# Edin_Usher_V2_0_ERM.net
KiCad netlist of a schematic drawn in EAGLE
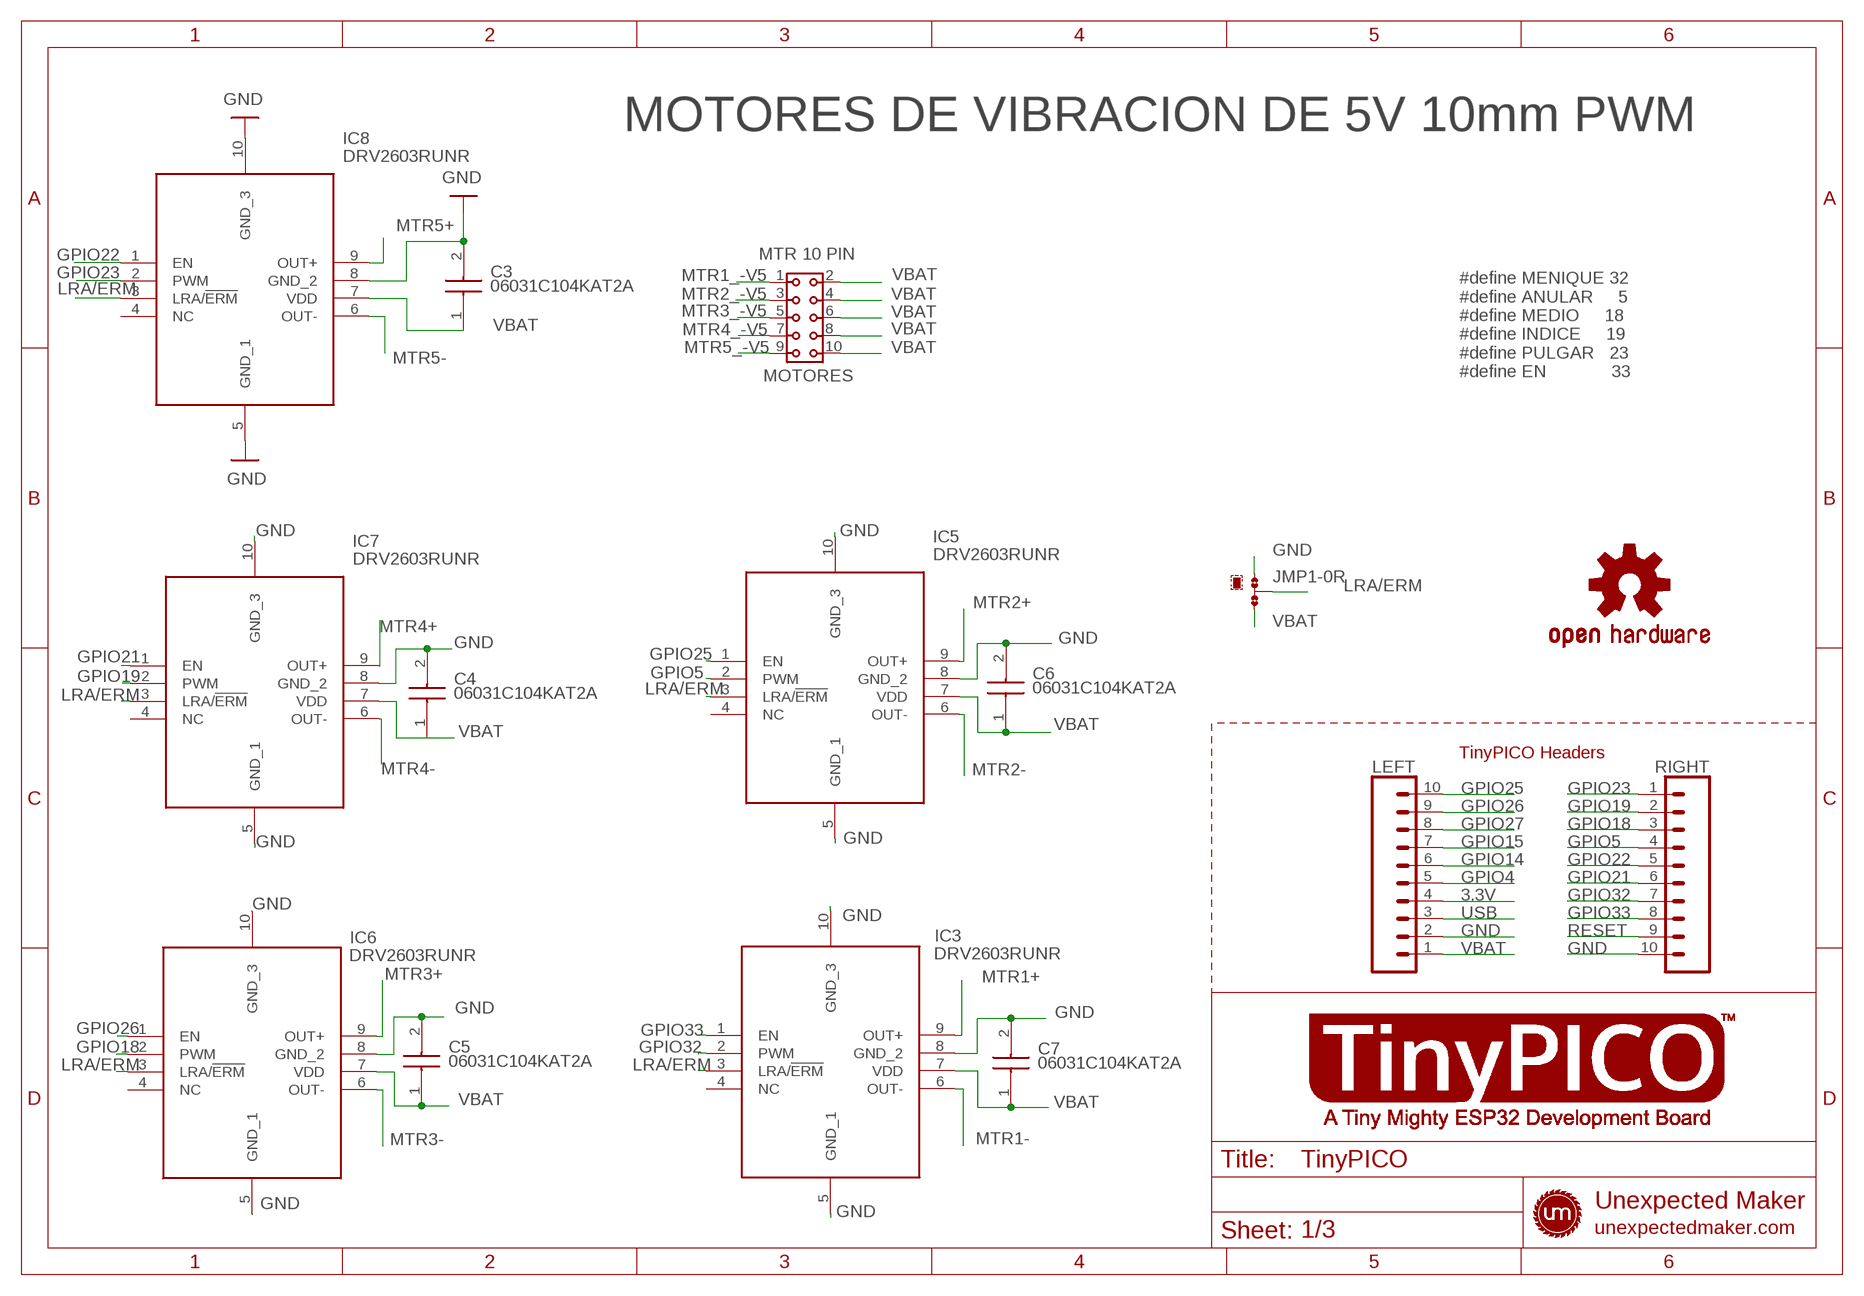
[diagram p0: schematic, sheet 1]
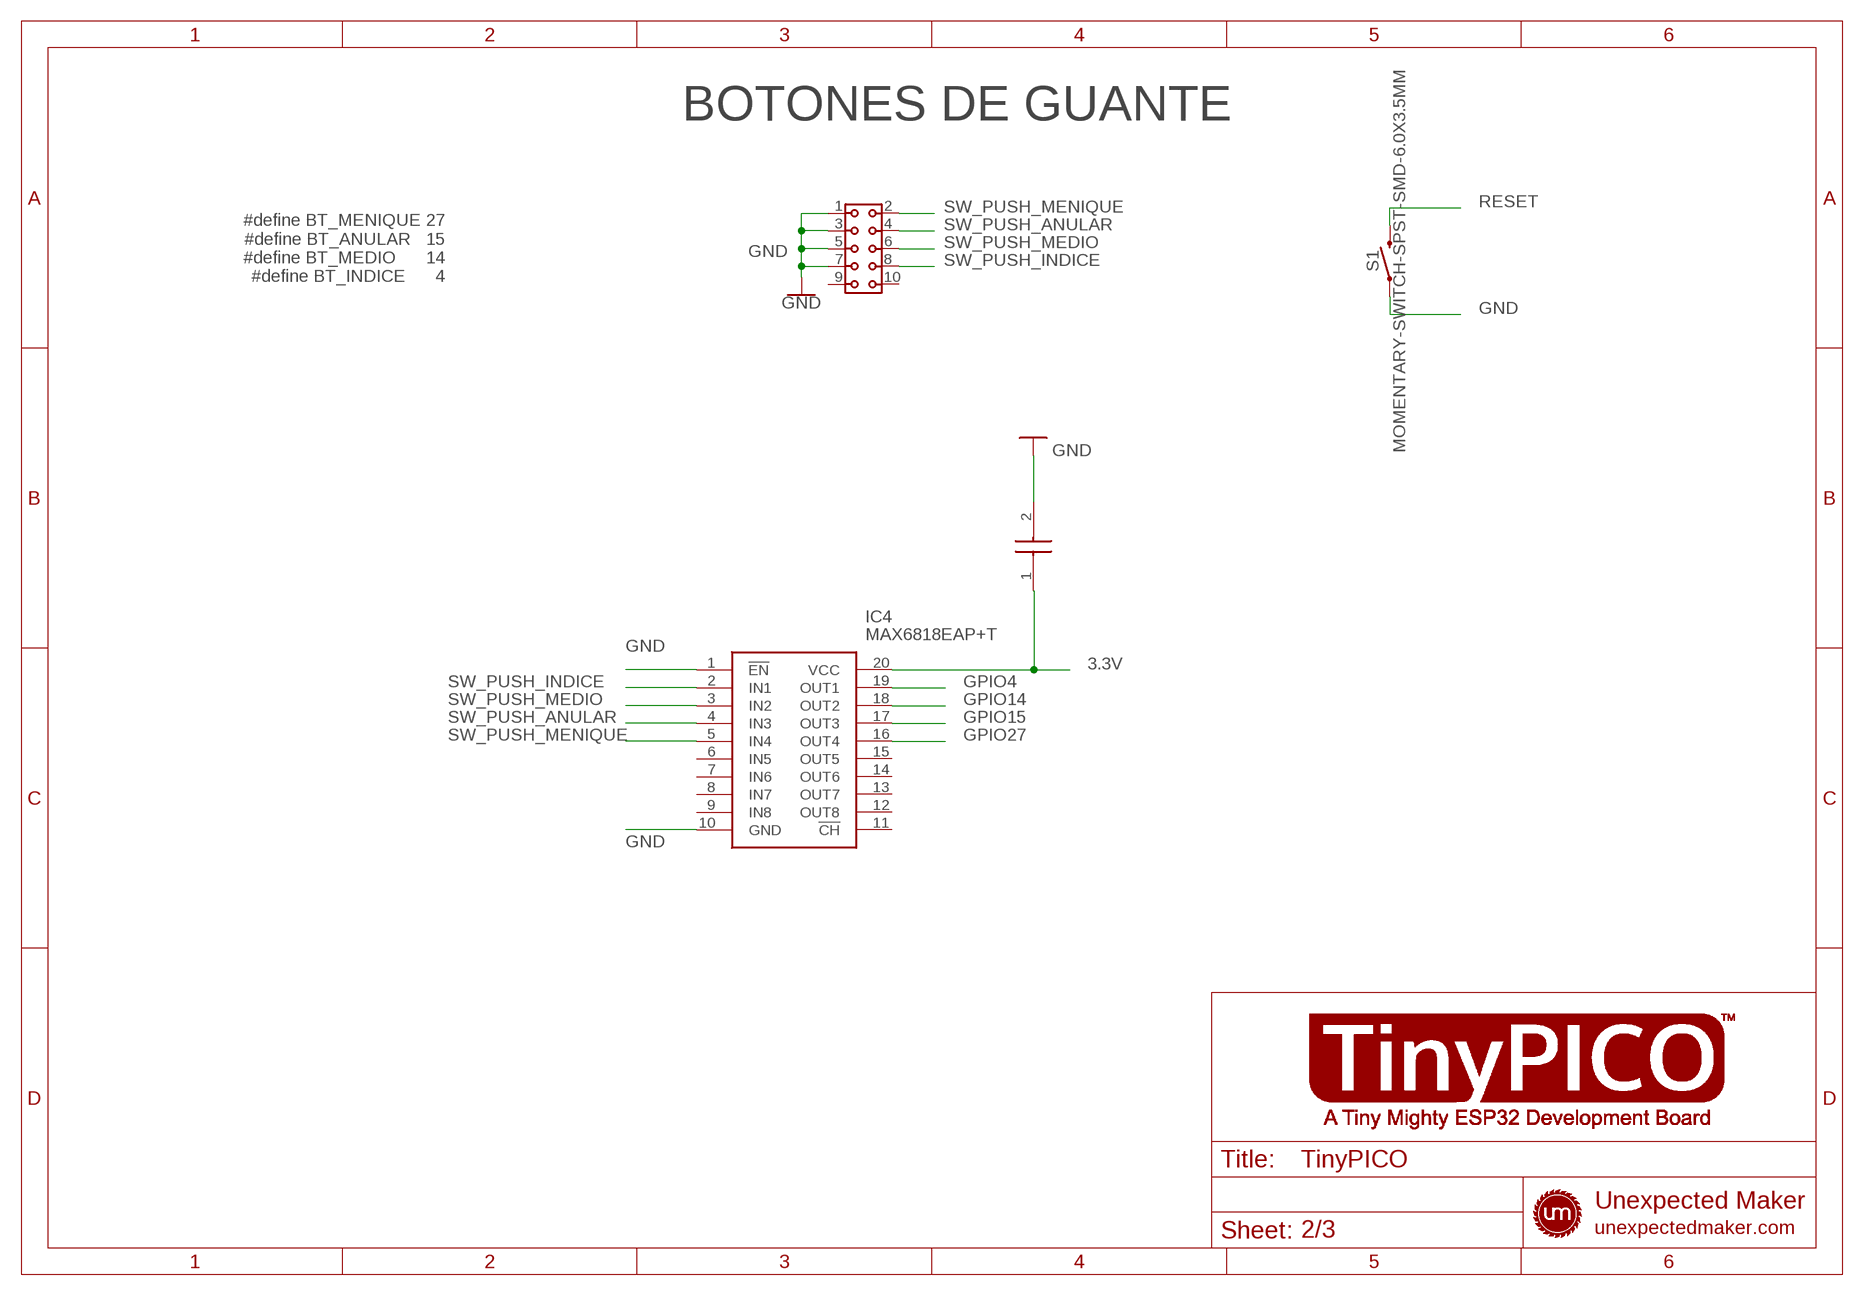
[diagram p1: schematic, sheet 2]
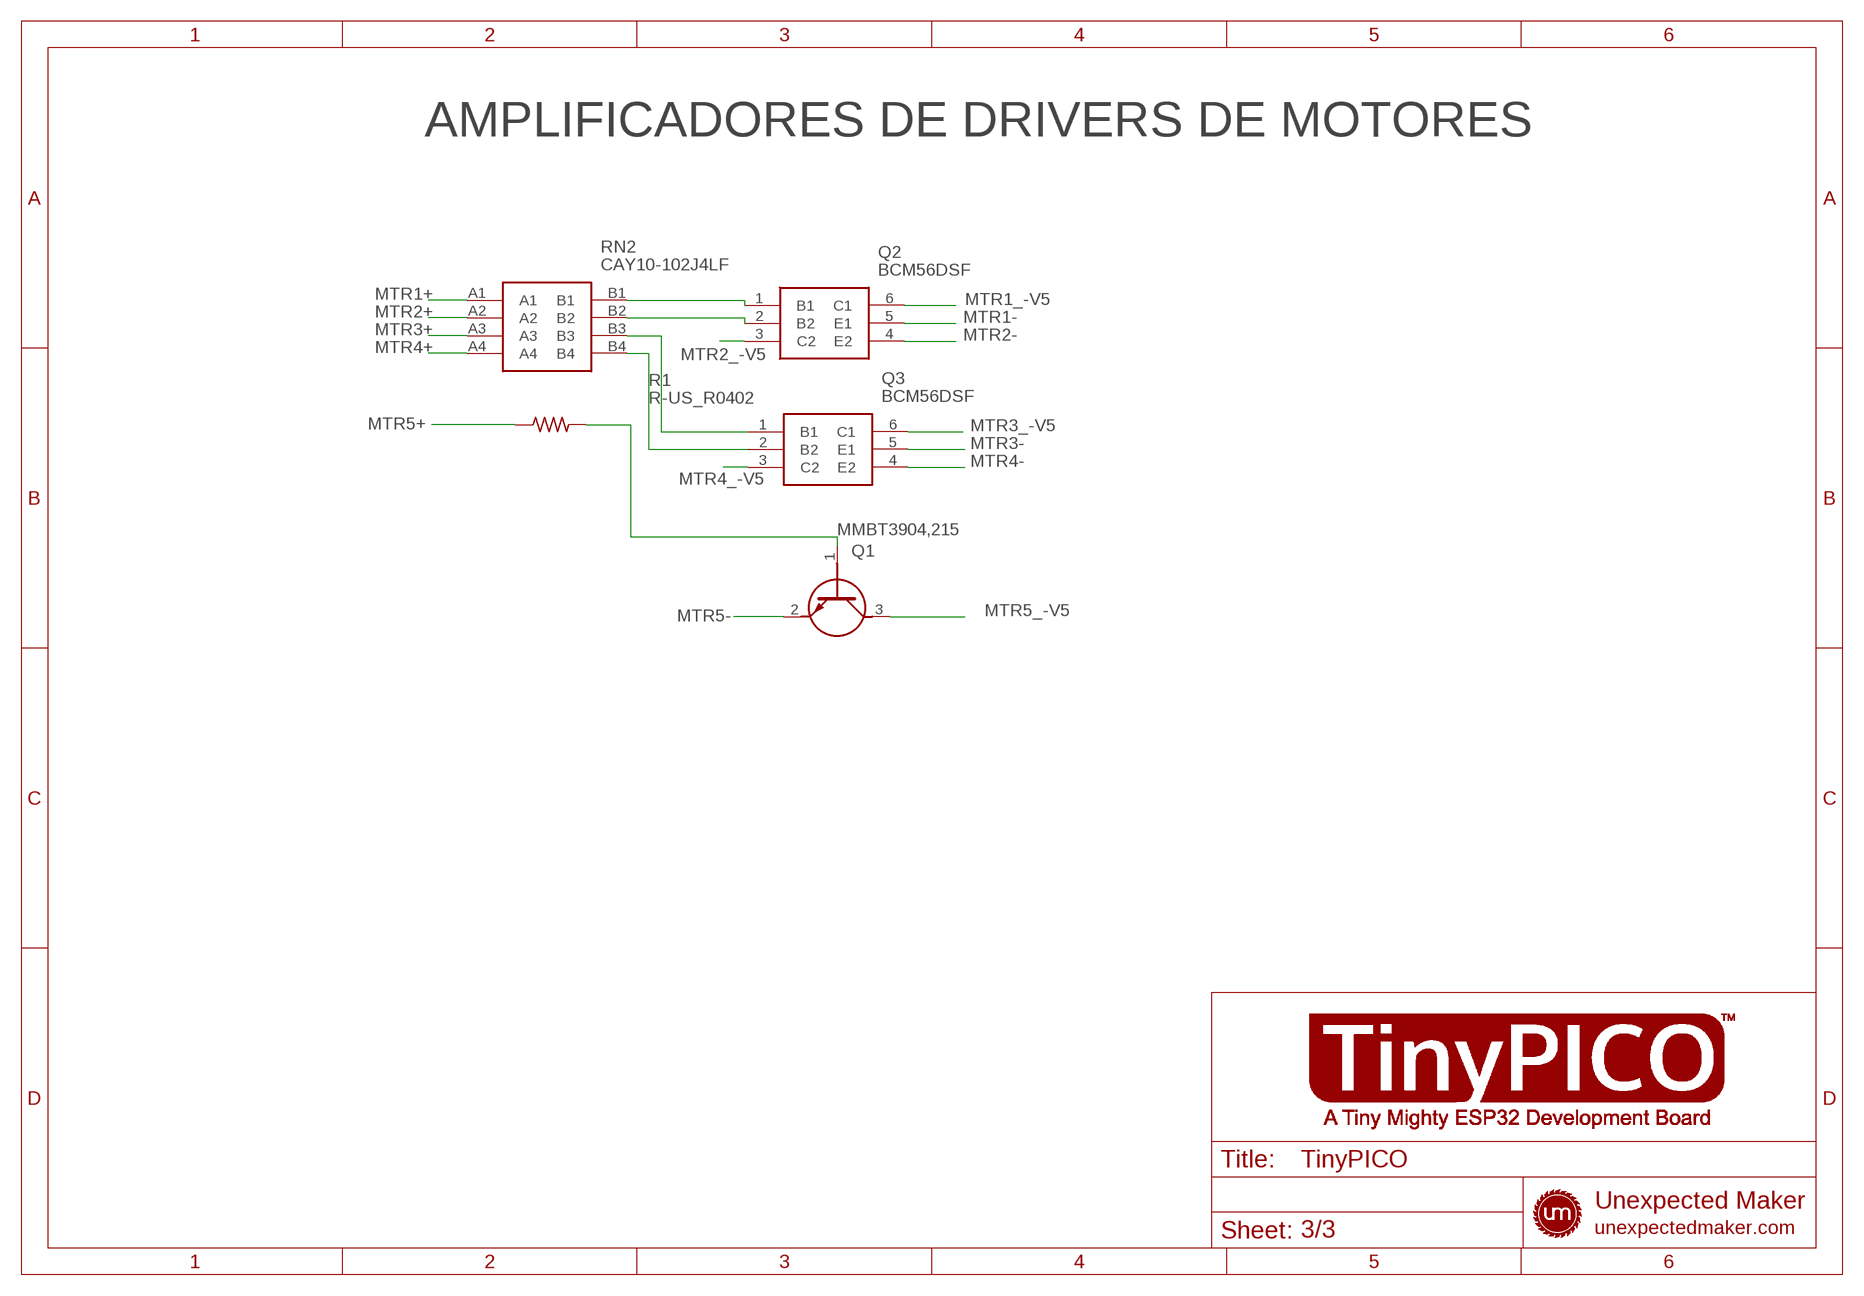
[diagram p2: schematic, sheet 3]

(export (version "E")
  (design (tool "Eeschema 10.0.6"))
  (components
    (comp (ref "C3")
      (value "06031C104KAT2A")
      (footprint "eagle-import:CAPC1608X90N")
      (fields (field (name "MOUSER_PART_NUMBER") "581-06031C104KAT2A"))
      (libsource (lib "eagle-import") (part "06031C104KAT2A"))
    )
    (comp (ref "C4")
      (value "06031C104KAT2A")
      (footprint "eagle-import:CAPC1608X90N")
      (fields (field (name "MOUSER_PART_NUMBER") "581-06031C104KAT2A"))
      (libsource (lib "eagle-import") (part "06031C104KAT2A"))
    )
    (comp (ref "C5")
      (value "06031C104KAT2A")
      (footprint "eagle-import:CAPC1608X90N")
      (fields (field (name "MOUSER_PART_NUMBER") "581-06031C104KAT2A"))
      (libsource (lib "eagle-import") (part "06031C104KAT2A"))
    )
    (comp (ref "C6")
      (value "06031C104KAT2A")
      (footprint "eagle-import:CAPC1608X90N")
      (fields (field (name "MOUSER_PART_NUMBER") "581-06031C104KAT2A"))
      (libsource (lib "eagle-import") (part "06031C104KAT2A"))
    )
    (comp (ref "C7")
      (value "06031C104KAT2A")
      (footprint "eagle-import:CAPC1608X90N")
      (fields (field (name "MOUSER_PART_NUMBER") "581-06031C104KAT2A"))
      (libsource (lib "eagle-import") (part "06031C104KAT2A"))
    )
    (comp (ref "IC3")
      (value "DRV2603RUNR")
      (footprint "eagle-import:QFN50P200X200X80-10N")
      (fields (field (name "MOUSER_PART_NUMBER") "595-DRV2603RUNR"))
      (libsource (lib "eagle-import") (part "DRV2603RUNR"))
    )
    (comp (ref "IC5")
      (value "DRV2603RUNR")
      (footprint "eagle-import:QFN50P200X200X80-10N")
      (fields (field (name "MOUSER_PART_NUMBER") "595-DRV2603RUNR"))
      (libsource (lib "eagle-import") (part "DRV2603RUNR"))
    )
    (comp (ref "IC6")
      (value "DRV2603RUNR")
      (footprint "eagle-import:QFN50P200X200X80-10N")
      (fields (field (name "MOUSER_PART_NUMBER") "595-DRV2603RUNR"))
      (libsource (lib "eagle-import") (part "DRV2603RUNR"))
    )
    (comp (ref "IC7")
      (value "DRV2603RUNR")
      (footprint "eagle-import:QFN50P200X200X80-10N")
      (fields (field (name "MOUSER_PART_NUMBER") "595-DRV2603RUNR"))
      (libsource (lib "eagle-import") (part "DRV2603RUNR"))
    )
    (comp (ref "IC8")
      (value "DRV2603RUNR")
      (footprint "eagle-import:QFN50P200X200X80-10N")
      (fields (field (name "MOUSER_PART_NUMBER") "595-DRV2603RUNR"))
      (libsource (lib "eagle-import") (part "DRV2603RUNR"))
    )
    (comp (ref "JMP1")
      (value "0R-JUMPA")
      (footprint "eagle-import:A0R-JMP")
      (libsource (lib "eagle-import") (part "0R-JUMPA"))
    )
    (comp (ref "LEFT")
      (value "TINYPICO_HEADER_10NO_SILK_PTH_FEMALE")
      (footprint "eagle-import:1X10_NO_SILK")
      (libsource (lib "eagle-import") (part "TINYPICO_HEADER_10NO_SILK_PTH_FEMALE"))
    )
    (comp (ref "LOGO1")
      (value "OSHW-LOGOS")
      (footprint "eagle-import:OSHW-LOGO-S")
      (libsource (lib "eagle-import") (part "OSHW-LOGOS"))
    )
    (comp (ref "MOTORES")
      (value "MTR 10 PIN")
      (footprint "eagle-import:61301021821")
      (libsource (lib "eagle-import") (part "6130XX21821_61301021821"))
    )
    (comp (ref "RIGHT")
      (value "TINYPICO_HEADER_10NO_SILK_PTH_FEMALE")
      (footprint "eagle-import:1X10_NO_SILK")
      (libsource (lib "eagle-import") (part "TINYPICO_HEADER_10NO_SILK_PTH_FEMALE"))
    )
    (comp (ref "Q1")
      (value "MMBT3904,215")
      (footprint "eagle-import:SOT95P230X110-3N")
      (fields (field (name "MOUSER_PART_NUMBER") "771-MMBT3904T/R"))
      (libsource (lib "eagle-import") (part "MMBT3904,215"))
    )
    (comp (ref "Q2")
      (value "BCM56DSF")
      (footprint "eagle-import:SOT95P275X110-6N")
      (fields (field (name "MOUSER_PART_NUMBER") "771-BCM56DSF"))
      (libsource (lib "eagle-import") (part "BCM56DSF"))
    )
    (comp (ref "Q3")
      (value "BCM56DSF")
      (footprint "eagle-import:SOT95P275X110-6N")
      (fields (field (name "MOUSER_PART_NUMBER") "771-BCM56DSF"))
      (libsource (lib "eagle-import") (part "BCM56DSF"))
    )
    (comp (ref "R1")
      (value "R-US_R0402")
      (footprint "eagle-import:R0402")
      (libsource (lib "eagle-import") (part "R-US_R0402"))
    )
    (comp (ref "RN2")
      (value "CAY10-102J4LF")
      (footprint "eagle-import:CAY10102J4LF")
      (fields (field (name "MOUSER_PART_NUMBER") "652-CAY10-102J4LF"))
      (libsource (lib "eagle-import") (part "CAY10-102J4LF"))
    )
    (comp (ref "BOTONES")
      (value "BTN 10 PIN")
      (footprint "eagle-import:61301021821")
      (libsource (lib "eagle-import") (part "6130XX21821_61301021821"))
    )
    (comp (ref "C8")
      (value "0603B104K160CT")
      (footprint "eagle-import:CAPC1608X87N")
      (fields (field (name "MOUSER_PART_NUMBER") "791-0603B104K160CT"))
      (libsource (lib "eagle-import") (part "0603B104K160CT"))
    )
    (comp (ref "IC4")
      (value "MAX6818EAP+T")
      (footprint "eagle-import:SOP65P778X199-20N")
      (fields (field (name "MOUSER_PART_NUMBER") "700-MAX6818EAPT"))
      (libsource (lib "eagle-import") (part "MAX6818EAP+T"))
    )
    (comp (ref "S1")
      (value "MOMENTARY-SWITCH-SPST-SMD-6.0X3.5MM")
      (footprint "eagle-import:TACTILE_SWITCH_SMD_6.0X3.5MM")
      (libsource (lib "eagle-import") (part "MOMENTARY-SWITCH-SPST-SMD-6.0X3.5MM"))
    )
  )
  (nets
    (net (code "1") (name "3.3V") (class "Default")
      (node (ref "C8") (pin "1") (pinfunction "1_1") (pintype "bidirectional"))
      (node (ref "IC4") (pin "20") (pinfunction "VCC_20") (pintype "power_in"))
      (node (ref "LEFT") (pin "4") (pinfunction "4_4") (pintype "passive"))
    )
    (net (code "2") (name "GND") (class "Default")
      (node (ref "BOTONES") (pin "1") (pinfunction "1_1") (pintype "passive"))
      (node (ref "BOTONES") (pin "3") (pinfunction "3_3") (pintype "passive"))
      (node (ref "BOTONES") (pin "5") (pinfunction "5_5") (pintype "passive"))
      (node (ref "BOTONES") (pin "7") (pinfunction "7_7") (pintype "passive"))
      (node (ref "C3") (pin "2") (pinfunction "2_2") (pintype "bidirectional"))
      (node (ref "C4") (pin "2") (pinfunction "2_2") (pintype "bidirectional"))
      (node (ref "C5") (pin "2") (pinfunction "2_2") (pintype "bidirectional"))
      (node (ref "C6") (pin "2") (pinfunction "2_2") (pintype "bidirectional"))
      (node (ref "C7") (pin "2") (pinfunction "2_2") (pintype "bidirectional"))
      (node (ref "C8") (pin "2") (pinfunction "2_2") (pintype "bidirectional"))
      (node (ref "IC3") (pin "10") (pinfunction "GND_3_10") (pintype "power_in"))
      (node (ref "IC3") (pin "5") (pinfunction "GND_1_5") (pintype "power_in"))
      (node (ref "IC3") (pin "8") (pinfunction "GND_2_8") (pintype "power_in"))
      (node (ref "IC4") (pin "1") (pinfunction "~{EN}_1") (pintype "input"))
      (node (ref "IC4") (pin "10") (pinfunction "GND_10") (pintype "power_in"))
      (node (ref "IC5") (pin "10") (pinfunction "GND_3_10") (pintype "power_in"))
      (node (ref "IC5") (pin "5") (pinfunction "GND_1_5") (pintype "power_in"))
      (node (ref "IC5") (pin "8") (pinfunction "GND_2_8") (pintype "power_in"))
      (node (ref "IC6") (pin "10") (pinfunction "GND_3_10") (pintype "power_in"))
      (node (ref "IC6") (pin "5") (pinfunction "GND_1_5") (pintype "power_in"))
      (node (ref "IC6") (pin "8") (pinfunction "GND_2_8") (pintype "power_in"))
      (node (ref "IC7") (pin "10") (pinfunction "GND_3_10") (pintype "power_in"))
      (node (ref "IC7") (pin "5") (pinfunction "GND_1_5") (pintype "power_in"))
      (node (ref "IC7") (pin "8") (pinfunction "GND_2_8") (pintype "power_in"))
      (node (ref "IC8") (pin "10") (pinfunction "GND_3_10") (pintype "power_in"))
      (node (ref "IC8") (pin "5") (pinfunction "GND_1_5") (pintype "power_in"))
      (node (ref "IC8") (pin "8") (pinfunction "GND_2_8") (pintype "power_in"))
      (node (ref "JMP1") (pin "1") (pinfunction "1_1") (pintype "passive"))
      (node (ref "LEFT") (pin "2") (pinfunction "2_2") (pintype "passive"))
      (node (ref "RIGHT") (pin "10") (pinfunction "10_10") (pintype "passive"))
      (node (ref "S1") (pin "1") (pinfunction "1_1") (pintype "passive"))
    )
    (net (code "3") (name "GPIO4") (class "Default")
      (node (ref "IC4") (pin "19") (pinfunction "OUT1_19") (pintype "output"))
      (node (ref "LEFT") (pin "5") (pinfunction "5_5") (pintype "passive"))
    )
    (net (code "4") (name "GPIO5") (class "Default")
      (node (ref "IC5") (pin "2") (pinfunction "PWM_2") (pintype "input"))
      (node (ref "RIGHT") (pin "4") (pinfunction "4_4") (pintype "passive"))
    )
    (net (code "5") (name "GPIO14") (class "Default")
      (node (ref "IC4") (pin "18") (pinfunction "OUT2_18") (pintype "output"))
      (node (ref "LEFT") (pin "6") (pinfunction "6_6") (pintype "passive"))
    )
    (net (code "6") (name "GPIO15") (class "Default")
      (node (ref "IC4") (pin "17") (pinfunction "OUT3_17") (pintype "output"))
      (node (ref "LEFT") (pin "7") (pinfunction "7_7") (pintype "passive"))
    )
    (net (code "7") (name "GPIO18") (class "Default")
      (node (ref "IC6") (pin "2") (pinfunction "PWM_2") (pintype "input"))
      (node (ref "RIGHT") (pin "3") (pinfunction "3_3") (pintype "passive"))
    )
    (net (code "8") (name "GPIO19") (class "Default")
      (node (ref "IC7") (pin "2") (pinfunction "PWM_2") (pintype "input"))
      (node (ref "RIGHT") (pin "2") (pinfunction "2_2") (pintype "passive"))
    )
    (net (code "9") (name "GPIO21") (class "Default")
      (node (ref "IC7") (pin "1") (pinfunction "EN_1") (pintype "input"))
      (node (ref "RIGHT") (pin "6") (pinfunction "6_6") (pintype "passive"))
    )
    (net (code "10") (name "GPIO22") (class "Default")
      (node (ref "IC8") (pin "1") (pinfunction "EN_1") (pintype "input"))
      (node (ref "RIGHT") (pin "5") (pinfunction "5_5") (pintype "passive"))
    )
    (net (code "11") (name "GPIO23") (class "Default")
      (node (ref "IC8") (pin "2") (pinfunction "PWM_2") (pintype "input"))
      (node (ref "RIGHT") (pin "1") (pinfunction "1_1") (pintype "passive"))
    )
    (net (code "12") (name "GPIO25") (class "Default")
      (node (ref "IC5") (pin "1") (pinfunction "EN_1") (pintype "input"))
      (node (ref "LEFT") (pin "10") (pinfunction "10_10") (pintype "passive"))
    )
    (net (code "13") (name "GPIO26") (class "Default")
      (node (ref "IC6") (pin "1") (pinfunction "EN_1") (pintype "input"))
      (node (ref "LEFT") (pin "9") (pinfunction "9_9") (pintype "passive"))
    )
    (net (code "14") (name "GPIO27") (class "Default")
      (node (ref "IC4") (pin "16") (pinfunction "OUT4_16") (pintype "output"))
      (node (ref "LEFT") (pin "8") (pinfunction "8_8") (pintype "passive"))
    )
    (net (code "15") (name "GPIO32") (class "Default")
      (node (ref "IC3") (pin "2") (pinfunction "PWM_2") (pintype "input"))
      (node (ref "RIGHT") (pin "7") (pinfunction "7_7") (pintype "passive"))
    )
    (net (code "16") (name "GPIO33") (class "Default")
      (node (ref "IC3") (pin "1") (pinfunction "EN_1") (pintype "input"))
      (node (ref "RIGHT") (pin "8") (pinfunction "8_8") (pintype "passive"))
    )
    (net (code "17") (name "LRA{slash}ERM") (class "Default")
      (node (ref "IC3") (pin "3") (pinfunction "LRA/~{ERM}_3") (pintype "input"))
      (node (ref "IC5") (pin "3") (pinfunction "LRA/~{ERM}_3") (pintype "input"))
      (node (ref "IC6") (pin "3") (pinfunction "LRA/~{ERM}_3") (pintype "input"))
      (node (ref "IC7") (pin "3") (pinfunction "LRA/~{ERM}_3") (pintype "input"))
      (node (ref "IC8") (pin "3") (pinfunction "LRA/~{ERM}_3") (pintype "input"))
      (node (ref "JMP1") (pin "2") (pinfunction "2_2") (pintype "passive"))
    )
    (net (code "18") (name "MTR1+") (class "Default")
      (node (ref "IC3") (pin "9") (pinfunction "OUT+_9") (pintype "output"))
      (node (ref "RN2") (pin "A1") (pinfunction "A1_A1") (pintype "bidirectional"))
    )
    (net (code "19") (name "MTR1-") (class "Default")
      (node (ref "IC3") (pin "6") (pinfunction "OUT-_6") (pintype "output"))
      (node (ref "Q2") (pin "5") (pinfunction "E1_5") (pintype "bidirectional"))
    )
    (net (code "20") (name "MTR1_-V5") (class "Default")
      (node (ref "MOTORES") (pin "1") (pinfunction "1_1") (pintype "passive"))
      (node (ref "Q2") (pin "6") (pinfunction "C1_6") (pintype "bidirectional"))
    )
    (net (code "21") (name "MTR2+") (class "Default")
      (node (ref "IC5") (pin "9") (pinfunction "OUT+_9") (pintype "output"))
      (node (ref "RN2") (pin "A2") (pinfunction "A2_A2") (pintype "bidirectional"))
    )
    (net (code "22") (name "MTR2-") (class "Default")
      (node (ref "IC5") (pin "6") (pinfunction "OUT-_6") (pintype "output"))
      (node (ref "Q2") (pin "4") (pinfunction "E2_4") (pintype "bidirectional"))
    )
    (net (code "23") (name "MTR2_-V5") (class "Default")
      (node (ref "MOTORES") (pin "3") (pinfunction "3_3") (pintype "passive"))
      (node (ref "Q2") (pin "3") (pinfunction "C2_3") (pintype "bidirectional"))
    )
    (net (code "24") (name "MTR3+") (class "Default")
      (node (ref "IC6") (pin "9") (pinfunction "OUT+_9") (pintype "output"))
      (node (ref "RN2") (pin "A3") (pinfunction "A3_A3") (pintype "bidirectional"))
    )
    (net (code "25") (name "MTR3-") (class "Default")
      (node (ref "IC6") (pin "6") (pinfunction "OUT-_6") (pintype "output"))
      (node (ref "Q3") (pin "5") (pinfunction "E1_5") (pintype "bidirectional"))
    )
    (net (code "26") (name "MTR3_-V5") (class "Default")
      (node (ref "MOTORES") (pin "5") (pinfunction "5_5") (pintype "passive"))
      (node (ref "Q3") (pin "6") (pinfunction "C1_6") (pintype "bidirectional"))
    )
    (net (code "27") (name "MTR4+") (class "Default")
      (node (ref "IC7") (pin "9") (pinfunction "OUT+_9") (pintype "output"))
      (node (ref "RN2") (pin "A4") (pinfunction "A4_A4") (pintype "bidirectional"))
    )
    (net (code "28") (name "MTR4-") (class "Default")
      (node (ref "IC7") (pin "6") (pinfunction "OUT-_6") (pintype "output"))
      (node (ref "Q3") (pin "4") (pinfunction "E2_4") (pintype "bidirectional"))
    )
    (net (code "29") (name "MTR4_-V5") (class "Default")
      (node (ref "MOTORES") (pin "7") (pinfunction "7_7") (pintype "passive"))
      (node (ref "Q3") (pin "3") (pinfunction "C2_3") (pintype "bidirectional"))
    )
    (net (code "30") (name "MTR5+") (class "Default")
      (node (ref "IC8") (pin "9") (pinfunction "OUT+_9") (pintype "output"))
      (node (ref "R1") (pin "1") (pinfunction "1_1") (pintype "passive"))
    )
    (net (code "31") (name "MTR5-") (class "Default")
      (node (ref "IC8") (pin "6") (pinfunction "OUT-_6") (pintype "output"))
      (node (ref "Q1") (pin "2") (pinfunction "E_2") (pintype "bidirectional"))
    )
    (net (code "32") (name "MTR5_-V5") (class "Default")
      (node (ref "MOTORES") (pin "9") (pinfunction "9_9") (pintype "passive"))
      (node (ref "Q1") (pin "3") (pinfunction "C_3") (pintype "bidirectional"))
    )
    (net (code "33") (name "Net-(Q1-B)") (class "Default")
      (node (ref "Q1") (pin "1") (pinfunction "B_1") (pintype "bidirectional"))
      (node (ref "R1") (pin "2") (pinfunction "2_2") (pintype "passive"))
    )
    (net (code "34") (name "Net-(Q2-B1)") (class "Default")
      (node (ref "Q2") (pin "1") (pinfunction "B1_1") (pintype "bidirectional"))
      (node (ref "RN2") (pin "B1") (pinfunction "B1_B1") (pintype "bidirectional"))
    )
    (net (code "35") (name "Net-(Q2-B2)") (class "Default")
      (node (ref "Q2") (pin "2") (pinfunction "B2_2") (pintype "bidirectional"))
      (node (ref "RN2") (pin "B2") (pinfunction "B2_B2") (pintype "bidirectional"))
    )
    (net (code "36") (name "Net-(Q3-B1)") (class "Default")
      (node (ref "Q3") (pin "1") (pinfunction "B1_1") (pintype "bidirectional"))
      (node (ref "RN2") (pin "B3") (pinfunction "B3_B3") (pintype "bidirectional"))
    )
    (net (code "37") (name "Net-(Q3-B2)") (class "Default")
      (node (ref "Q3") (pin "2") (pinfunction "B2_2") (pintype "bidirectional"))
      (node (ref "RN2") (pin "B4") (pinfunction "B4_B4") (pintype "bidirectional"))
    )
    (net (code "38") (name "RESET") (class "Default")
      (node (ref "RIGHT") (pin "9") (pinfunction "9_9") (pintype "passive"))
      (node (ref "S1") (pin "2") (pinfunction "2_2") (pintype "passive"))
    )
    (net (code "39") (name "SW_PUSH_ANULAR") (class "Default")
      (node (ref "BOTONES") (pin "4") (pinfunction "4_4") (pintype "passive"))
      (node (ref "IC4") (pin "4") (pinfunction "IN3_4") (pintype "input"))
    )
    (net (code "40") (name "SW_PUSH_INDICE") (class "Default")
      (node (ref "BOTONES") (pin "8") (pinfunction "8_8") (pintype "passive"))
      (node (ref "IC4") (pin "2") (pinfunction "IN1_2") (pintype "input"))
    )
    (net (code "41") (name "SW_PUSH_MEDIO") (class "Default")
      (node (ref "BOTONES") (pin "6") (pinfunction "6_6") (pintype "passive"))
      (node (ref "IC4") (pin "3") (pinfunction "IN2_3") (pintype "input"))
    )
    (net (code "42") (name "SW_PUSH_MENIQUE") (class "Default")
      (node (ref "BOTONES") (pin "2") (pinfunction "2_2") (pintype "passive"))
      (node (ref "IC4") (pin "5") (pinfunction "IN4_5") (pintype "input"))
    )
    (net (code "43") (name "USB") (class "Default")
      (node (ref "LEFT") (pin "3") (pinfunction "3_3") (pintype "passive"))
    )
    (net (code "44") (name "VBAT") (class "Default")
      (node (ref "C3") (pin "1") (pinfunction "1_1") (pintype "bidirectional"))
      (node (ref "C4") (pin "1") (pinfunction "1_1") (pintype "bidirectional"))
      (node (ref "C5") (pin "1") (pinfunction "1_1") (pintype "bidirectional"))
      (node (ref "C6") (pin "1") (pinfunction "1_1") (pintype "bidirectional"))
      (node (ref "C7") (pin "1") (pinfunction "1_1") (pintype "bidirectional"))
      (node (ref "IC3") (pin "7") (pinfunction "VDD_7") (pintype "power_in"))
      (node (ref "IC5") (pin "7") (pinfunction "VDD_7") (pintype "power_in"))
      (node (ref "IC6") (pin "7") (pinfunction "VDD_7") (pintype "power_in"))
      (node (ref "IC7") (pin "7") (pinfunction "VDD_7") (pintype "power_in"))
      (node (ref "IC8") (pin "7") (pinfunction "VDD_7") (pintype "power_in"))
      (node (ref "JMP1") (pin "3") (pinfunction "3_3") (pintype "passive"))
      (node (ref "LEFT") (pin "1") (pinfunction "1_1") (pintype "passive"))
      (node (ref "MOTORES") (pin "10") (pinfunction "10_10") (pintype "passive"))
      (node (ref "MOTORES") (pin "2") (pinfunction "2_2") (pintype "passive"))
      (node (ref "MOTORES") (pin "4") (pinfunction "4_4") (pintype "passive"))
      (node (ref "MOTORES") (pin "6") (pinfunction "6_6") (pintype "passive"))
      (node (ref "MOTORES") (pin "8") (pinfunction "8_8") (pintype "passive"))
    )
    (net (code "45") (name "unconnected-(BOTONES-Pad9)") (class "Default")
      (node (ref "BOTONES") (pin "9") (pinfunction "9_9") (pintype "passive"))
    )
    (net (code "46") (name "unconnected-(BOTONES-Pad10)") (class "Default")
      (node (ref "BOTONES") (pin "10") (pinfunction "10_10") (pintype "passive"))
    )
    (net (code "47") (name "unconnected-(IC3-NC-Pad4)") (class "Default")
      (node (ref "IC3") (pin "4") (pinfunction "NC_4") (pintype "no_connect"))
    )
    (net (code "48") (name "unconnected-(IC4-IN5-Pad6)") (class "Default")
      (node (ref "IC4") (pin "6") (pinfunction "IN5_6") (pintype "input"))
    )
    (net (code "49") (name "unconnected-(IC4-IN6-Pad7)") (class "Default")
      (node (ref "IC4") (pin "7") (pinfunction "IN6_7") (pintype "input"))
    )
    (net (code "50") (name "unconnected-(IC4-IN7-Pad8)") (class "Default")
      (node (ref "IC4") (pin "8") (pinfunction "IN7_8") (pintype "input"))
    )
    (net (code "51") (name "unconnected-(IC4-IN8-Pad9)") (class "Default")
      (node (ref "IC4") (pin "9") (pinfunction "IN8_9") (pintype "input"))
    )
    (net (code "52") (name "unconnected-(IC4-OUT5-Pad15)") (class "Default")
      (node (ref "IC4") (pin "15") (pinfunction "OUT5_15") (pintype "output"))
    )
    (net (code "53") (name "unconnected-(IC4-OUT6-Pad14)") (class "Default")
      (node (ref "IC4") (pin "14") (pinfunction "OUT6_14") (pintype "output"))
    )
    (net (code "54") (name "unconnected-(IC4-OUT7-Pad13)") (class "Default")
      (node (ref "IC4") (pin "13") (pinfunction "OUT7_13") (pintype "output"))
    )
    (net (code "55") (name "unconnected-(IC4-OUT8-Pad12)") (class "Default")
      (node (ref "IC4") (pin "12") (pinfunction "OUT8_12") (pintype "output"))
    )
    (net (code "56") (name "unconnected-(IC4-~{CH}-Pad11)") (class "Default")
      (node (ref "IC4") (pin "11") (pinfunction "~{CH}_11") (pintype "output"))
    )
    (net (code "57") (name "unconnected-(IC5-NC-Pad4)") (class "Default")
      (node (ref "IC5") (pin "4") (pinfunction "NC_4") (pintype "no_connect"))
    )
    (net (code "58") (name "unconnected-(IC6-NC-Pad4)") (class "Default")
      (node (ref "IC6") (pin "4") (pinfunction "NC_4") (pintype "no_connect"))
    )
    (net (code "59") (name "unconnected-(IC7-NC-Pad4)") (class "Default")
      (node (ref "IC7") (pin "4") (pinfunction "NC_4") (pintype "no_connect"))
    )
    (net (code "60") (name "unconnected-(IC8-NC-Pad4)") (class "Default")
      (node (ref "IC8") (pin "4") (pinfunction "NC_4") (pintype "no_connect"))
    )
  )
)
